# source_eagle.net
KiCad netlist of a schematic drawn in EAGLE
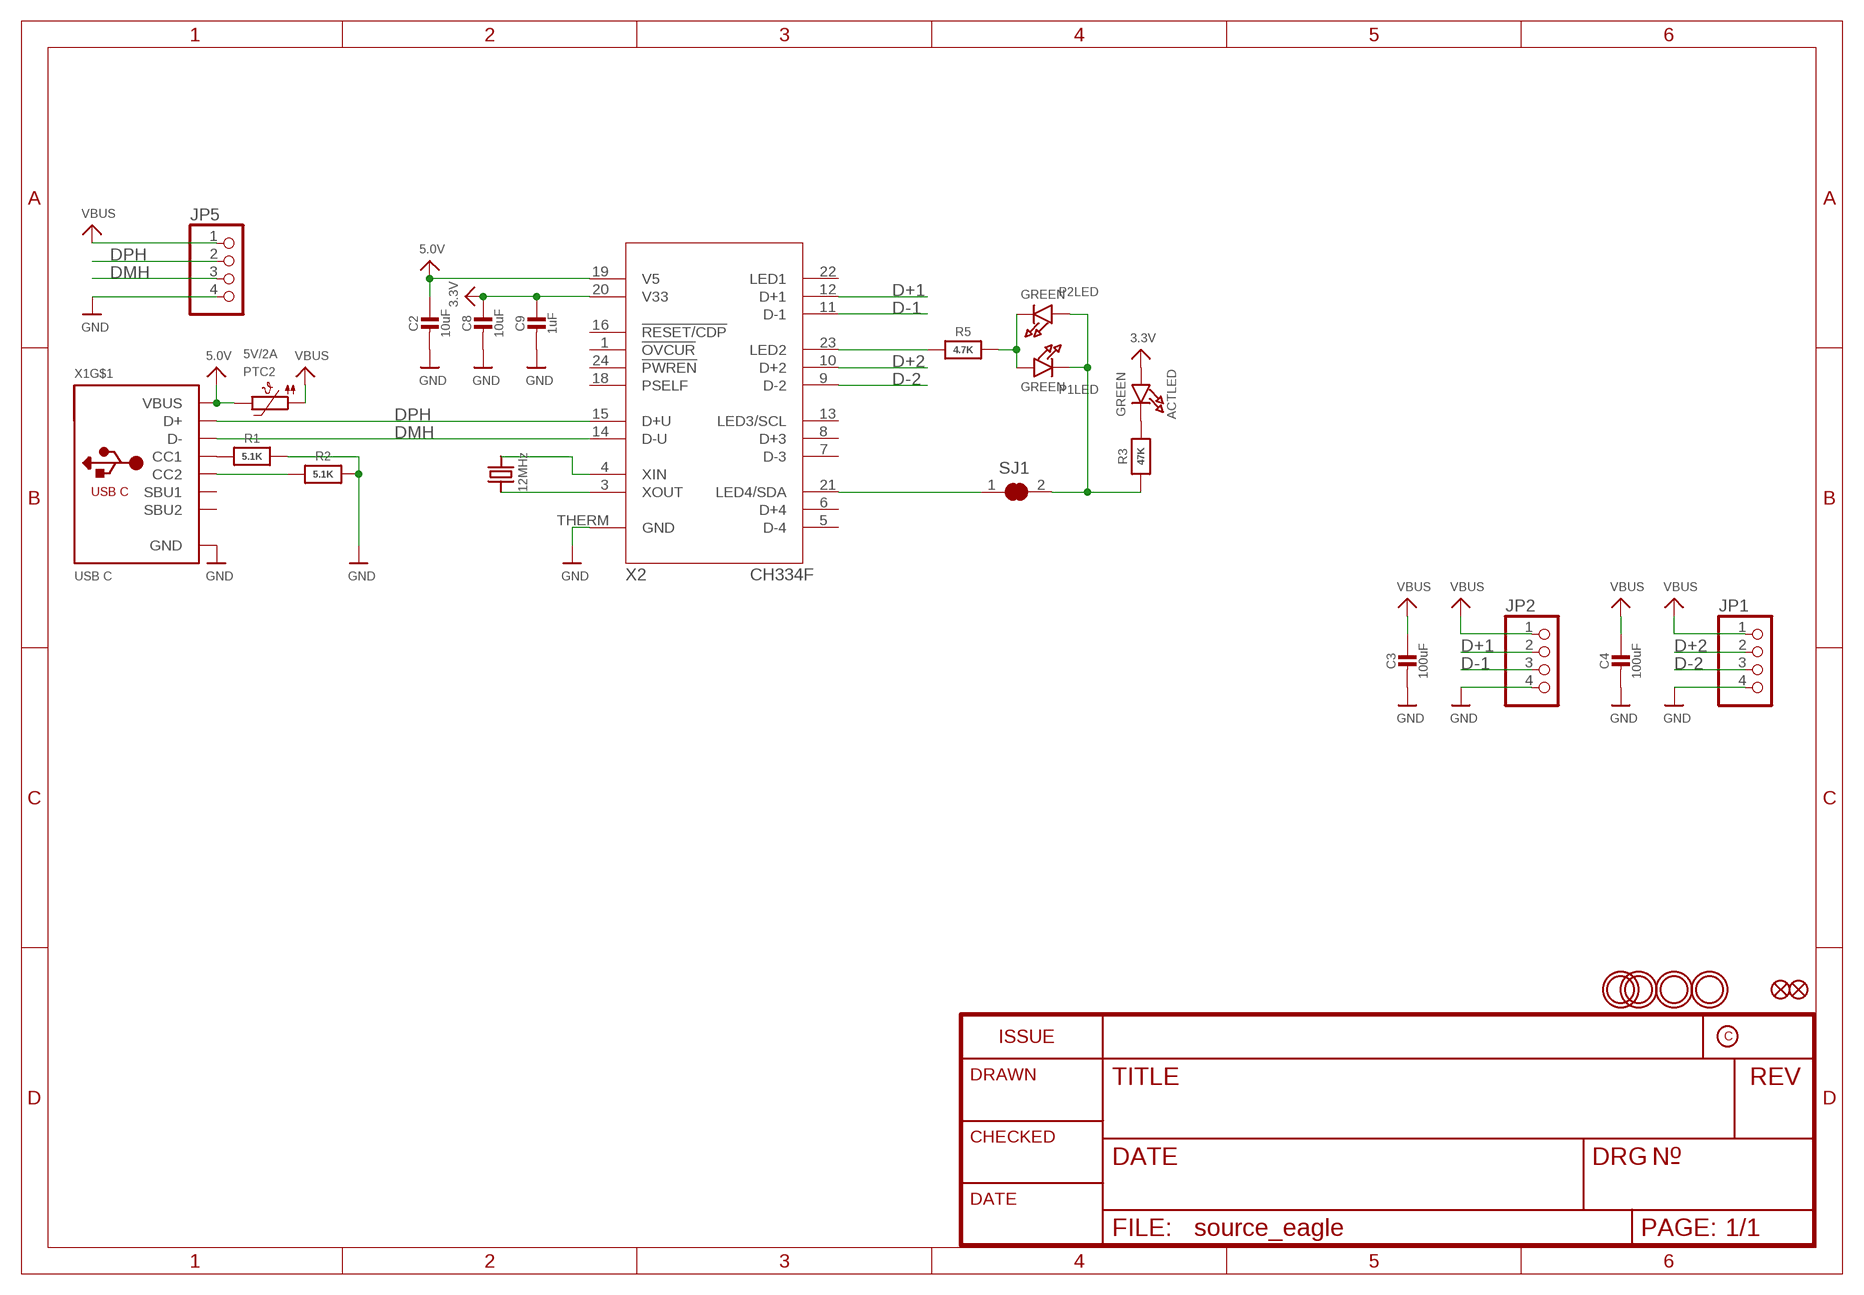
[diagram p0: schematic, sheet 1]

(export (version "E")
  (design (tool "Eeschema 10.0.6"))
  (components
    (comp (ref "ACTLED")
      (value "GREEN")
      (footprint "eagle-import:CHIPLED_0603_NOOUTLINE")
      (libsource (lib "eagle-import") (part "LED0603_NOOUTLINE"))
    )
    (comp (ref "C2")
      (value "10uF")
      (footprint "eagle-import:0805-NO")
      (libsource (lib "eagle-import") (part "CAP_CERAMIC0805-NOOUTLINE"))
    )
    (comp (ref "C3")
      (value "100uF")
      (footprint "eagle-import:_1206")
      (libsource (lib "eagle-import") (part "CAP_CERAMIC_1206"))
    )
    (comp (ref "C4")
      (value "100uF")
      (footprint "eagle-import:_1206")
      (libsource (lib "eagle-import") (part "CAP_CERAMIC_1206"))
    )
    (comp (ref "C8")
      (value "10uF")
      (footprint "eagle-import:0805-NO")
      (libsource (lib "eagle-import") (part "CAP_CERAMIC0805-NOOUTLINE"))
    )
    (comp (ref "C9")
      (value "1uF")
      (footprint "eagle-import:0603-NO")
      (libsource (lib "eagle-import") (part "CAP_CERAMIC0603_NO"))
    )
    (comp (ref "FID1")
      (value "FIDUCIAL_0.5MM")
      (footprint "eagle-import:FIDUCIAL_0.5MM")
      (libsource (lib "eagle-import") (part "FIDUCIAL_0.5MM"))
    )
    (comp (ref "FID2")
      (value "FIDUCIAL_0.5MM")
      (footprint "eagle-import:FIDUCIAL_0.5MM")
      (libsource (lib "eagle-import") (part "FIDUCIAL_0.5MM"))
    )
    (comp (ref "JP1")
      (value "HEADER-1X4ROUND")
      (footprint "eagle-import:1X04_ROUND")
      (libsource (lib "eagle-import") (part "HEADER-1X4ROUND"))
    )
    (comp (ref "JP2")
      (value "HEADER-1X4ROUND")
      (footprint "eagle-import:1X04_ROUND")
      (libsource (lib "eagle-import") (part "HEADER-1X4ROUND"))
    )
    (comp (ref "JP5")
      (value "HEADER-1X4ROUND")
      (footprint "eagle-import:1X04_ROUND")
      (libsource (lib "eagle-import") (part "HEADER-1X4ROUND"))
    )
    (comp (ref "P1LED")
      (value "GREEN")
      (footprint "eagle-import:CHIPLED_0603_NOOUTLINE")
      (libsource (lib "eagle-import") (part "LED0603_NOOUTLINE"))
    )
    (comp (ref "P2LED")
      (value "GREEN")
      (footprint "eagle-import:CHIPLED_0603_NOOUTLINE")
      (libsource (lib "eagle-import") (part "LED0603_NOOUTLINE"))
    )
    (comp (ref "PTC2")
      (value "5V/2A")
      (footprint "eagle-import:0805-NO")
      (libsource (lib "eagle-import") (part "PTC_0805"))
    )
    (comp (ref "R1")
      (value "5.1K")
      (footprint "eagle-import:0603-NO")
      (libsource (lib "eagle-import") (part "RESISTOR_0603_NOOUT"))
    )
    (comp (ref "R2")
      (value "5.1K")
      (footprint "eagle-import:0603-NO")
      (libsource (lib "eagle-import") (part "RESISTOR_0603_NOOUT"))
    )
    (comp (ref "R3")
      (value "47K")
      (footprint "eagle-import:0603-NO")
      (libsource (lib "eagle-import") (part "RESISTOR_0603_NOOUT"))
    )
    (comp (ref "R5")
      (value "4.7K")
      (footprint "eagle-import:0603-NO")
      (libsource (lib "eagle-import") (part "RESISTOR_0603_NOOUT"))
    )
    (comp (ref "SJ1")
      (value "SOLDERJUMPER_CLOSED")
      (footprint "eagle-import:SOLDERJUMPER_CLOSEDWIRE")
      (libsource (lib "eagle-import") (part "SOLDERJUMPER_CLOSED"))
    )
    (comp (ref "U$23")
      (value "MOUNTINGHOLE2.5")
      (footprint "eagle-import:MOUNTINGHOLE_2.5_PLATED")
      (libsource (lib "eagle-import") (part "MOUNTINGHOLE2.5"))
    )
    (comp (ref "U$28")
      (value "MOUNTINGHOLE2.5")
      (footprint "eagle-import:MOUNTINGHOLE_2.5_PLATED")
      (libsource (lib "eagle-import") (part "MOUNTINGHOLE2.5"))
    )
    (comp (ref "U$29")
      (value "MOUNTINGHOLE2.5")
      (footprint "eagle-import:MOUNTINGHOLE_2.5_PLATED")
      (libsource (lib "eagle-import") (part "MOUNTINGHOLE2.5"))
    )
    (comp (ref "U$31")
      (value "MOUNTINGHOLE2.5")
      (footprint "eagle-import:MOUNTINGHOLE_2.5_PLATED")
      (libsource (lib "eagle-import") (part "MOUNTINGHOLE2.5"))
    )
    (comp (ref "X1")
      (value "USB C")
      (footprint "eagle-import:USB_C_CUSB31-CFM2AX-01-X")
      (libsource (lib "eagle-import") (part "USB_C"))
    )
    (comp (ref "X2")
      (value "CH334F")
      (footprint "eagle-import:QFN24_4MM")
      (libsource (lib "eagle-import") (part "CH334F"))
    )
    (comp (ref "Y1")
      (value "12MHz")
      (footprint "eagle-import:CRYSTAL_2.5X2")
      (libsource (lib "eagle-import") (part "CRYSTAL2.5X2.0"))
    )
  )
  (nets
    (net (code "1") (name "/D+1") (class "Default")
      (node (ref "JP2") (pin "2") (pinfunction "2_2") (pintype "passive"))
      (node (ref "X2") (pin "12") (pinfunction "D+1_12") (pintype "bidirectional"))
    )
    (net (code "2") (name "/D+2") (class "Default")
      (node (ref "JP1") (pin "2") (pinfunction "2_2") (pintype "passive"))
      (node (ref "X2") (pin "10") (pinfunction "D+2_10") (pintype "bidirectional"))
    )
    (net (code "3") (name "/D-1") (class "Default")
      (node (ref "JP2") (pin "3") (pinfunction "3_3") (pintype "passive"))
      (node (ref "X2") (pin "11") (pinfunction "D-1_11") (pintype "bidirectional"))
    )
    (net (code "4") (name "/D-2") (class "Default")
      (node (ref "JP1") (pin "3") (pinfunction "3_3") (pintype "passive"))
      (node (ref "X2") (pin "9") (pinfunction "D-2_9") (pintype "bidirectional"))
    )
    (net (code "5") (name "/DMH") (class "Default")
      (node (ref "JP5") (pin "3") (pinfunction "3_3") (pintype "passive"))
      (node (ref "X1") (pin "A7") (pinfunction "D-_A7") (pintype "bidirectional"))
      (node (ref "X1") (pin "B7") (pinfunction "D-_B7") (pintype "bidirectional"))
      (node (ref "X2") (pin "14") (pinfunction "D-U_14") (pintype "bidirectional"))
    )
    (net (code "6") (name "/DPH") (class "Default")
      (node (ref "JP5") (pin "2") (pinfunction "2_2") (pintype "passive"))
      (node (ref "X1") (pin "A6") (pinfunction "D+_A6") (pintype "bidirectional"))
      (node (ref "X1") (pin "B6") (pinfunction "D+_B6") (pintype "bidirectional"))
      (node (ref "X2") (pin "15") (pinfunction "D+U_15") (pintype "bidirectional"))
    )
    (net (code "7") (name "3.3V") (class "Default")
      (node (ref "ACTLED") (pin "A") (pinfunction "A_A") (pintype "passive"))
      (node (ref "C8") (pin "1") (pinfunction "1_1") (pintype "passive"))
      (node (ref "C9") (pin "1") (pinfunction "1_1") (pintype "passive"))
      (node (ref "X2") (pin "20") (pinfunction "V33_20") (pintype "power_in"))
    )
    (net (code "8") (name "5.0V") (class "Default")
      (node (ref "C2") (pin "1") (pinfunction "1_1") (pintype "passive"))
      (node (ref "PTC2") (pin "2") (pinfunction "2_2") (pintype "passive"))
      (node (ref "X1") (pin "A4B9") (pinfunction "VBUS_A4B9") (pintype "power_in"))
      (node (ref "X1") (pin "B4A9") (pinfunction "VBUS_B4A9") (pintype "power_in"))
      (node (ref "X2") (pin "19") (pinfunction "V5_19") (pintype "power_in"))
    )
    (net (code "9") (name "GND") (class "Default")
      (node (ref "C2") (pin "2") (pinfunction "2_2") (pintype "passive"))
      (node (ref "C3") (pin "2") (pinfunction "2_2") (pintype "passive"))
      (node (ref "C4") (pin "2") (pinfunction "2_2") (pintype "passive"))
      (node (ref "C8") (pin "2") (pinfunction "2_2") (pintype "passive"))
      (node (ref "C9") (pin "2") (pinfunction "2_2") (pintype "passive"))
      (node (ref "JP1") (pin "4") (pinfunction "4_4") (pintype "passive"))
      (node (ref "JP2") (pin "4") (pinfunction "4_4") (pintype "passive"))
      (node (ref "JP5") (pin "4") (pinfunction "4_4") (pintype "passive"))
      (node (ref "R1") (pin "2") (pinfunction "2_2") (pintype "passive"))
      (node (ref "R2") (pin "2") (pinfunction "2_2") (pintype "passive"))
      (node (ref "X1") (pin "A1B12") (pinfunction "GND_A1B12") (pintype "power_in"))
      (node (ref "X1") (pin "B1A12") (pinfunction "GND_B1A12") (pintype "power_in"))
      (node (ref "X2") (pin "THERM") (pinfunction "GND_THERM") (pintype "power_in"))
    )
    (net (code "10") (name "Net-(ACTLED-PadC)") (class "Default")
      (node (ref "ACTLED") (pin "C") (pinfunction "C_C") (pintype "passive"))
      (node (ref "R3") (pin "2") (pinfunction "2_2") (pintype "passive"))
    )
    (net (code "11") (name "Net-(P1LED-PadA)") (class "Default")
      (node (ref "P1LED") (pin "A") (pinfunction "A_A") (pintype "passive"))
      (node (ref "P2LED") (pin "C") (pinfunction "C_C") (pintype "passive"))
      (node (ref "R5") (pin "2") (pinfunction "2_2") (pintype "passive"))
    )
    (net (code "12") (name "Net-(P1LED-PadC)") (class "Default")
      (node (ref "P1LED") (pin "C") (pinfunction "C_C") (pintype "passive"))
      (node (ref "P2LED") (pin "A") (pinfunction "A_A") (pintype "passive"))
      (node (ref "R3") (pin "1") (pinfunction "1_1") (pintype "passive"))
      (node (ref "SJ1") (pin "2") (pinfunction "2_2") (pintype "passive"))
    )
    (net (code "13") (name "Net-(X1A-CC1)") (class "Default")
      (node (ref "R1") (pin "1") (pinfunction "1_1") (pintype "passive"))
      (node (ref "X1") (pin "A5") (pinfunction "CC1_A5") (pintype "bidirectional"))
    )
    (net (code "14") (name "Net-(X1A-CC2)") (class "Default")
      (node (ref "R2") (pin "1") (pinfunction "1_1") (pintype "passive"))
      (node (ref "X1") (pin "B5") (pinfunction "CC2_B5") (pintype "bidirectional"))
    )
    (net (code "15") (name "Net-(X2-LED2)") (class "Default")
      (node (ref "R5") (pin "1") (pinfunction "1_1") (pintype "passive"))
      (node (ref "X2") (pin "23") (pinfunction "LED2_23") (pintype "bidirectional"))
    )
    (net (code "16") (name "Net-(X2-LED4{slash}SDA)") (class "Default")
      (node (ref "SJ1") (pin "1") (pinfunction "1_1") (pintype "passive"))
      (node (ref "X2") (pin "21") (pinfunction "LED4/SDA_21") (pintype "bidirectional"))
    )
    (net (code "17") (name "Net-(X2-XIN)") (class "Default")
      (node (ref "X2") (pin "4") (pinfunction "XIN_4") (pintype "input"))
      (node (ref "Y1") (pin "3") (pinfunction "2_3") (pintype "passive"))
    )
    (net (code "18") (name "Net-(X2-XOUT)") (class "Default")
      (node (ref "X2") (pin "3") (pinfunction "XOUT_3") (pintype "output"))
      (node (ref "Y1") (pin "1") (pinfunction "1_1") (pintype "passive"))
    )
    (net (code "19") (name "VBUS") (class "Default")
      (node (ref "C3") (pin "1") (pinfunction "1_1") (pintype "passive"))
      (node (ref "C4") (pin "1") (pinfunction "1_1") (pintype "passive"))
      (node (ref "JP1") (pin "1") (pinfunction "1_1") (pintype "passive"))
      (node (ref "JP2") (pin "1") (pinfunction "1_1") (pintype "passive"))
      (node (ref "JP5") (pin "1") (pinfunction "1_1") (pintype "passive"))
      (node (ref "PTC2") (pin "1") (pinfunction "1_1") (pintype "passive"))
    )
    (net (code "20") (name "unconnected-(X1A-SBU1-PadA8)") (class "Default")
      (node (ref "X1") (pin "A8") (pinfunction "SBU1_A8") (pintype "bidirectional"))
    )
    (net (code "21") (name "unconnected-(X1A-SBU2-PadB8)") (class "Default")
      (node (ref "X1") (pin "B8") (pinfunction "SBU2_B8") (pintype "bidirectional"))
    )
    (net (code "22") (name "unconnected-(X2-D+3-Pad8)") (class "Default")
      (node (ref "X2") (pin "8") (pinfunction "D+3_8") (pintype "bidirectional"))
    )
    (net (code "23") (name "unconnected-(X2-D+4-Pad6)") (class "Default")
      (node (ref "X2") (pin "6") (pinfunction "D+4_6") (pintype "bidirectional"))
    )
    (net (code "24") (name "unconnected-(X2-D-3-Pad7)") (class "Default")
      (node (ref "X2") (pin "7") (pinfunction "D-3_7") (pintype "bidirectional"))
    )
    (net (code "25") (name "unconnected-(X2-D-4-Pad5)") (class "Default")
      (node (ref "X2") (pin "5") (pinfunction "D-4_5") (pintype "bidirectional"))
    )
    (net (code "26") (name "unconnected-(X2-LED1-Pad22)") (class "Default")
      (node (ref "X2") (pin "22") (pinfunction "LED1_22") (pintype "bidirectional"))
    )
    (net (code "27") (name "unconnected-(X2-LED3{slash}SCL-Pad13)") (class "Default")
      (node (ref "X2") (pin "13") (pinfunction "LED3/SCL_13") (pintype "bidirectional"))
    )
    (net (code "28") (name "unconnected-(X2-PSELF-Pad18)") (class "Default")
      (node (ref "X2") (pin "18") (pinfunction "PSELF_18") (pintype "input"))
    )
    (net (code "29") (name "unconnected-(X2-~{OVCUR}-Pad1)") (class "Default")
      (node (ref "X2") (pin "1") (pinfunction "~{OVCUR}_1") (pintype "input"))
    )
    (net (code "30") (name "unconnected-(X2-~{PWREN}-Pad24)") (class "Default")
      (node (ref "X2") (pin "24") (pinfunction "~{PWREN}_24") (pintype "output"))
    )
    (net (code "31") (name "unconnected-(X2-~{RESET{slash}CDP}-Pad16)") (class "Default")
      (node (ref "X2") (pin "16") (pinfunction "~{RESET/CDP}_16") (pintype "input"))
    )
  )
)
